# DigitSegment_Schematic.net
KiCad netlist of a schematic drawn in Altium Designer
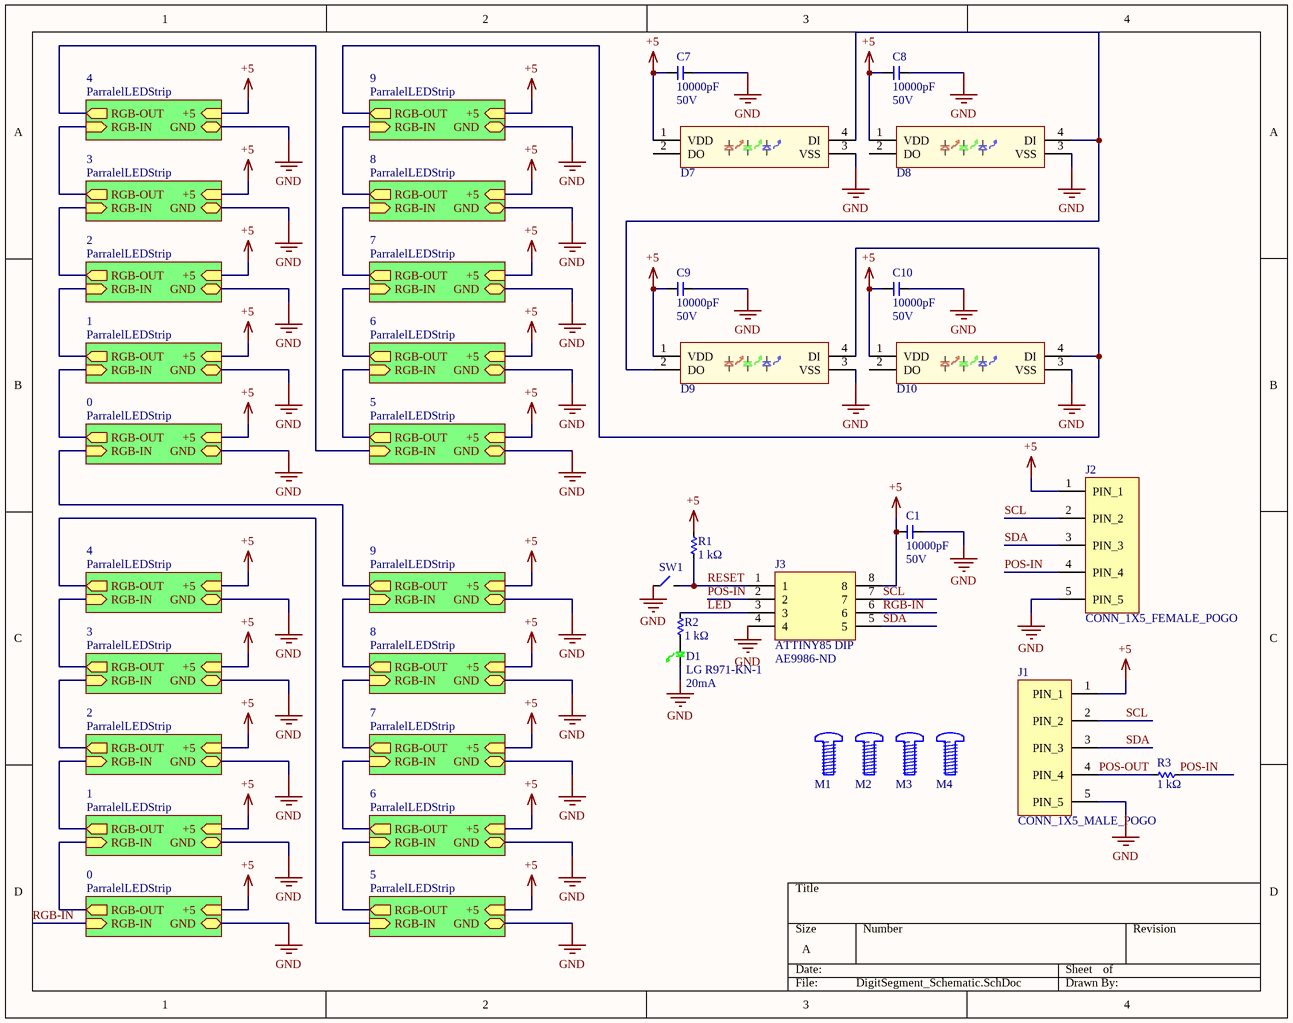
[diagram p0: DigitSegment_Schematic.SchDoc]

(export (version "E")
  (design (tool "Eeschema 10.0.6"))
  (components
    (comp (ref "C1")
      (value "__template_cap")
      (footprint "C0805")
      (fields
        (field (name "CAPACITANCE (SHORTHAND)") "10000pF")
        (field (name "RATED VOLTAGE") "50V")
        (field (name "MANUFACTURER") "Murata Electronics North America")
      )
      (libsource (lib "passives") (part "__template_cap"))
    )
    (comp (ref "C7")
      (value "__template_cap")
      (footprint "C0805")
      (fields
        (field (name "CAPACITANCE (SHORTHAND)") "10000pF")
        (field (name "RATED VOLTAGE") "50V")
        (field (name "MANUFACTURER") "Murata Electronics North America")
      )
      (libsource (lib "passives") (part "__template_cap"))
    )
    (comp (ref "C8")
      (value "__template_cap")
      (footprint "C0805")
      (fields
        (field (name "CAPACITANCE (SHORTHAND)") "10000pF")
        (field (name "RATED VOLTAGE") "50V")
        (field (name "MANUFACTURER") "Murata Electronics North America")
      )
      (libsource (lib "passives") (part "__template_cap"))
    )
    (comp (ref "C9")
      (value "__template_cap")
      (footprint "C0805")
      (fields
        (field (name "CAPACITANCE (SHORTHAND)") "10000pF")
        (field (name "RATED VOLTAGE") "50V")
        (field (name "MANUFACTURER") "Murata Electronics North America")
      )
      (libsource (lib "passives") (part "__template_cap"))
    )
    (comp (ref "C10")
      (value "__template_cap")
      (footprint "C0805")
      (fields
        (field (name "CAPACITANCE (SHORTHAND)") "10000pF")
        (field (name "RATED VOLTAGE") "50V")
        (field (name "MANUFACTURER") "Murata Electronics North America")
      )
      (libsource (lib "passives") (part "__template_cap"))
    )
    (comp (ref "D1")
      (value "LED_LY971")
      (footprint "0805_Diode")
      (description "LED 0805 GREEN 20MA")
      (fields
        (field (name "MANUFACTURER") "OSRAM Opto Semiconductors Inc")
        (field (name "MANUFACTURER PART NUMBER") "LG R971-KN-1")
        (field (name "CURRENT - TEST") "20mA")
      )
      (libsource (lib "SSI") (part "LED_LY971"))
    )
    (comp (ref "D7")
      (value "LED_WS2812B")
      (footprint "4DFN5X5_WGS2812B")
      (description "LED RGB WS2812B")
      (libsource (lib "SSI") (part "LED_WS2812B"))
    )
    (comp (ref "D8")
      (value "LED_WS2812B")
      (footprint "4DFN5X5_WGS2812B")
      (description "LED RGB WS2812B")
      (libsource (lib "SSI") (part "LED_WS2812B"))
    )
    (comp (ref "D9")
      (value "LED_WS2812B")
      (footprint "4DFN5X5_WGS2812B")
      (description "LED RGB WS2812B")
      (libsource (lib "SSI") (part "LED_WS2812B"))
    )
    (comp (ref "D10")
      (value "LED_WS2812B")
      (footprint "4DFN5X5_WGS2812B")
      (description "LED RGB WS2812B")
      (libsource (lib "SSI") (part "LED_WS2812B"))
    )
    (comp (ref "J1")
      (value "CONN_1X5_MALE_POGO")
      (footprint "CONN_1X5_MALE_POGO")
      (description "RIGHT ANGLE .050\" GRID SLC")
      (libsource (lib "SSI") (part "CONN_1X5_MALE_POGO"))
    )
    (comp (ref "J2")
      (value "CONN_1X5_FEMALE_POGO")
      (footprint "CONN_1X5_FEMALE_POGO")
      (description ".050\" RA TARGET CONNECTOR")
      (libsource (lib "SSI") (part "CONN_1X5_FEMALE_POGO"))
    )
    (comp (ref "J3")
      (value "ATTINY85 DIP")
      (footprint "DIP8")
      (description "CONN IC SOCKET 8POS DIP TIN")
      (fields
        (field (name "MANUFACTURER") "Assmann WSW Components")
        (field (name "MANUFACTURER PART NUMBER") "A 08-LC-TT")
        (field (name "SUPPLIER PART NUMBER 1") "AE9986-ND")
      )
      (libsource (lib "SSI") (part "CONN_DIP_8"))
    )
    (comp (ref "M1")
      (value "SCREW_#2-56_5/16")
      (footprint "#2_HOLE")
      (description "#2-56 Button Head Screw, 5/16\"")
      (libsource (lib "SSI") (part "SCREW_#2-56_5/16"))
    )
    (comp (ref "M2")
      (value "SCREW_#2-56_5/16")
      (footprint "#2_HOLE")
      (description "#2-56 Button Head Screw, 5/16\"")
      (libsource (lib "SSI") (part "SCREW_#2-56_5/16"))
    )
    (comp (ref "M3")
      (value "SCREW_#2-56_5/16")
      (footprint "#2_HOLE")
      (description "#2-56 Button Head Screw, 5/16\"")
      (libsource (lib "SSI") (part "SCREW_#2-56_5/16"))
    )
    (comp (ref "M4")
      (value "SCREW_#2-56_5/16")
      (footprint "#2_HOLE")
      (description "#2-56 Button Head Screw, 5/16\"")
      (libsource (lib "SSI") (part "SCREW_#2-56_5/16"))
    )
    (comp (ref "R1")
      (value "__template_resistor")
      (footprint "R0805")
      (fields
        (field (name "RESISTANCE") "1 kΩ")
        (field (name "MANUFACTURER PART NUMBER") "RC0805FR-071KL")
        (field (name "MANUFACTURER") "Yageo")
        (field (name "TOLERANCE") "±1%")
      )
      (libsource (lib "passives") (part "__template_resistor"))
    )
    (comp (ref "R2")
      (value "__template_resistor")
      (footprint "R0805")
      (fields
        (field (name "RESISTANCE") "1 kΩ")
        (field (name "MANUFACTURER PART NUMBER") "RC0805FR-071KL")
        (field (name "MANUFACTURER") "Yageo")
        (field (name "TOLERANCE") "±1%")
      )
      (libsource (lib "passives") (part "__template_resistor"))
    )
    (comp (ref "R3")
      (value "__template_resistor")
      (footprint "R0805")
      (fields
        (field (name "RESISTANCE") "1 kΩ")
        (field (name "MANUFACTURER PART NUMBER") "RC0805FR-071KL")
        (field (name "MANUFACTURER") "Yageo")
        (field (name "TOLERANCE") "±1%")
      )
      (libsource (lib "passives") (part "__template_resistor"))
    )
    (comp (ref "SW1")
      (value "SWITCH_FSM4JSMATR")
      (footprint "SWITCH_FSM4JSMATR")
      (description "SWITCH TACTILE SPST-NO 0.05A 12V")
      (fields
        (field (name "MANUFACTURER") "TE Connectivity")
        (field (name "MANUFACTURER PART NUMBER") "FSM4JSMATR")
      )
      (libsource (lib "SSI") (part "SWITCH_FSM4JSMATR"))
    )
  )
  (nets
    (net (code "1") (name "+5") (class "Default")
      (node (ref "C1") (pin "1") (pintype "passive"))
      (node (ref "C10") (pin "1") (pintype "passive"))
      (node (ref "C7") (pin "1") (pintype "passive"))
      (node (ref "C8") (pin "1") (pintype "passive"))
      (node (ref "C9") (pin "1") (pintype "passive"))
      (node (ref "D10") (pin "1") (pinfunction "VDD_1") (pintype "passive"))
      (node (ref "D7") (pin "1") (pinfunction "VDD_1") (pintype "passive"))
      (node (ref "D8") (pin "1") (pinfunction "VDD_1") (pintype "passive"))
      (node (ref "D9") (pin "1") (pinfunction "VDD_1") (pintype "passive"))
      (node (ref "J1") (pin "1") (pinfunction "PIN_1_1") (pintype "power_in"))
      (node (ref "J2") (pin "1") (pinfunction "PIN_1_1") (pintype "power_in"))
      (node (ref "J3") (pin "8") (pinfunction "8_8") (pintype "power_in"))
      (node (ref "R1") (pin "2") (pintype "passive"))
    )
    (net (code "2") (name "/LED") (class "Default")
      (node (ref "J3") (pin "3") (pinfunction "3_3") (pintype "power_in"))
      (node (ref "R2") (pin "2") (pintype "passive"))
    )
    (net (code "3") (name "/POS-IN") (class "Default")
      (node (ref "J2") (pin "4") (pinfunction "PIN_4_4") (pintype "power_in"))
      (node (ref "J3") (pin "2") (pinfunction "2_2") (pintype "power_in"))
      (node (ref "R3") (pin "2") (pintype "passive"))
    )
    (net (code "4") (name "/POS-OUT") (class "Default")
      (node (ref "J1") (pin "4") (pinfunction "PIN_4_4") (pintype "power_in"))
      (node (ref "R3") (pin "1") (pintype "passive"))
    )
    (net (code "5") (name "/RESET") (class "Default")
      (node (ref "J3") (pin "1") (pinfunction "1_1") (pintype "power_in"))
      (node (ref "R1") (pin "1") (pintype "passive"))
      (node (ref "SW1") (pin "2") (pintype "passive"))
    )
    (net (code "6") (name "/RGB-IN") (class "Default")
      (node (ref "J3") (pin "6") (pinfunction "6_6") (pintype "power_in"))
    )
    (net (code "8") (name "/RGB-OUT_1") (class "Default")
      (node (ref "D10") (pin "4") (pinfunction "DI_4") (pintype "passive"))
      (node (ref "D9") (pin "4") (pinfunction "DI_4") (pintype "passive"))
    )
    (net (code "27") (name "/SCL") (class "Default")
      (node (ref "J1") (pin "2") (pinfunction "PIN_2_2") (pintype "power_in"))
      (node (ref "J2") (pin "2") (pinfunction "PIN_2_2") (pintype "power_in"))
      (node (ref "J3") (pin "7") (pinfunction "7_7") (pintype "power_in"))
    )
    (net (code "28") (name "/SDA") (class "Default")
      (node (ref "J1") (pin "3") (pinfunction "PIN_3_3") (pintype "power_in"))
      (node (ref "J2") (pin "3") (pinfunction "PIN_3_3") (pintype "power_in"))
      (node (ref "J3") (pin "5") (pinfunction "5_5") (pintype "power_in"))
    )
    (net (code "29") (name "GND") (class "Default")
      (node (ref "C1") (pin "2") (pintype "passive"))
      (node (ref "C10") (pin "2") (pintype "passive"))
      (node (ref "C7") (pin "2") (pintype "passive"))
      (node (ref "C8") (pin "2") (pintype "passive"))
      (node (ref "C9") (pin "2") (pintype "passive"))
      (node (ref "D1") (pin "1") (pintype "passive"))
      (node (ref "D10") (pin "3") (pinfunction "VSS_3") (pintype "passive"))
      (node (ref "D7") (pin "3") (pinfunction "VSS_3") (pintype "passive"))
      (node (ref "D8") (pin "3") (pinfunction "VSS_3") (pintype "passive"))
      (node (ref "D9") (pin "3") (pinfunction "VSS_3") (pintype "passive"))
      (node (ref "J1") (pin "5") (pinfunction "PIN_5_5") (pintype "power_in"))
      (node (ref "J2") (pin "5") (pinfunction "PIN_5_5") (pintype "power_in"))
      (node (ref "J3") (pin "4") (pinfunction "4_4") (pintype "power_in"))
      (node (ref "SW1") (pin "1") (pintype "passive"))
    )
    (net (code "30") (name "Net-(D1-Pad2)") (class "Default")
      (node (ref "D1") (pin "2") (pintype "passive"))
      (node (ref "R2") (pin "1") (pintype "passive"))
    )
    (net (code "31") (name "Net-(D7-DI)") (class "Default")
      (node (ref "D7") (pin "4") (pinfunction "DI_4") (pintype "passive"))
      (node (ref "D8") (pin "4") (pinfunction "DI_4") (pintype "passive"))
      (node (ref "D9") (pin "2") (pinfunction "DO_2") (pintype "passive"))
    )
    (net (code "32") (name "unconnected-(D7-DO-Pad2)") (class "Default")
      (node (ref "D7") (pin "2") (pinfunction "DO_2") (pintype "passive"))
    )
    (net (code "33") (name "unconnected-(D8-DO-Pad2)") (class "Default")
      (node (ref "D8") (pin "2") (pinfunction "DO_2") (pintype "passive"))
    )
    (net (code "34") (name "unconnected-(D10-DO-Pad2)") (class "Default")
      (node (ref "D10") (pin "2") (pinfunction "DO_2") (pintype "passive"))
    )
    (net (code "35") (name "unconnected-(M1-0-PadHOLE)") (class "Default")
      (node (ref "M1") (pin "HOLE") (pinfunction "0_HOLE") (pintype "passive"))
    )
    (net (code "36") (name "unconnected-(M2-0-PadHOLE)") (class "Default")
      (node (ref "M2") (pin "HOLE") (pinfunction "0_HOLE") (pintype "passive"))
    )
    (net (code "37") (name "unconnected-(M3-0-PadHOLE)") (class "Default")
      (node (ref "M3") (pin "HOLE") (pinfunction "0_HOLE") (pintype "passive"))
    )
    (net (code "38") (name "unconnected-(M4-0-PadHOLE)") (class "Default")
      (node (ref "M4") (pin "HOLE") (pinfunction "0_HOLE") (pintype "passive"))
    )
  )
)
